# ExternalRAM.net
KiCad netlist of a schematic drawn in Altium Designer
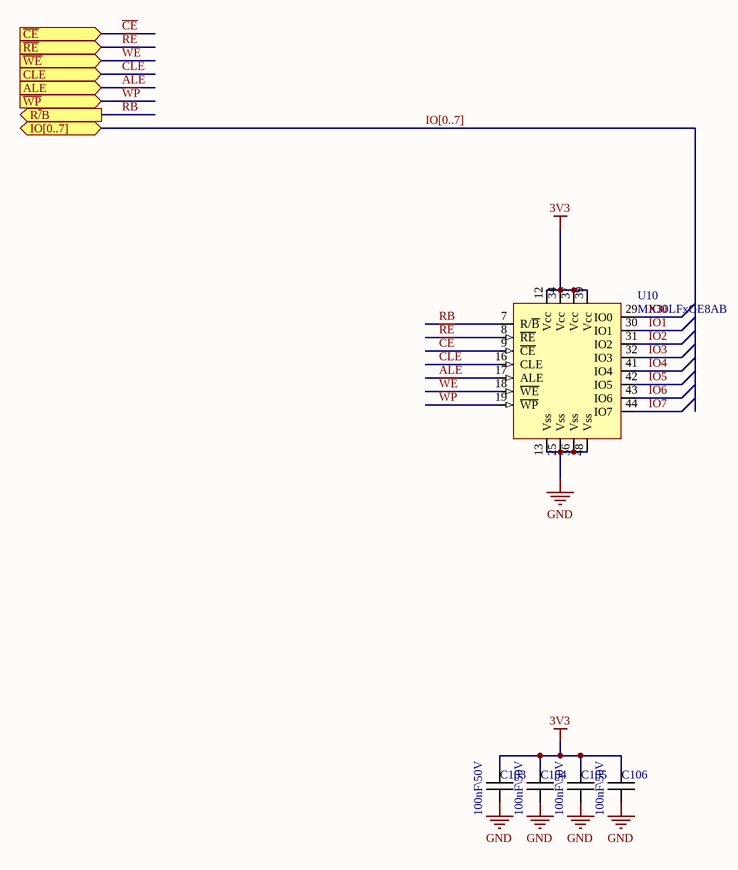
[diagram p0: ExternalRAM.SchDoc]

(export (version "E")
  (design (tool "Eeschema 10.0.6"))
  (components
    (comp (ref "C103")
      (value "100n~{F}50V")
      (footprint "SMD 0603")
      (description "CC0603KRX7R9BB104")
      (libsource (lib "Maks_lib") (part "Capasitor"))
    )
    (comp (ref "C104")
      (value "100n~{F}50V")
      (footprint "SMD 0603")
      (description "CC0603KRX7R9BB104")
      (libsource (lib "Maks_lib") (part "Capasitor"))
    )
    (comp (ref "C105")
      (value "100n~{F}50V")
      (footprint "SMD 0603")
      (description "CC0603KRX7R9BB104")
      (libsource (lib "Maks_lib") (part "Capasitor"))
    )
    (comp (ref "C106")
      (value "100n~{F}50V")
      (footprint "SMD 0603")
      (description "CC0603KRX7R9BB104")
      (libsource (lib "Maks_lib") (part "Capasitor"))
    )
    (comp (ref "U10")
      (value "MX30LFxGE8AB")
      (footprint "TSSOP50P2000X120-48N")
      (description "1G/2G/4G-bit NAND Flash Memory  (ECC-Free)")
      (libsource (lib "Maks_lib") (part "MX30LFxGE8AB"))
    )
  )
  (nets
    (net (code "1") (name "/ALE") (class "Default")
      (node (ref "U10") (pin "17") (pinfunction "ALE_17") (pintype "input"))
    )
    (net (code "2") (name "/CE") (class "Default")
      (node (ref "U10") (pin "9") (pinfunction "CE_9") (pintype "input"))
    )
    (net (code "3") (name "/CLE") (class "Default")
      (node (ref "U10") (pin "16") (pinfunction "CLE_16") (pintype "input"))
    )
    (net (code "4") (name "/IO0") (class "Default")
      (node (ref "U10") (pin "29") (pinfunction "IO0_29") (pintype "bidirectional"))
    )
    (net (code "5") (name "/IO1") (class "Default")
      (node (ref "U10") (pin "30") (pinfunction "IO1_30") (pintype "bidirectional"))
    )
    (net (code "6") (name "/IO2") (class "Default")
      (node (ref "U10") (pin "31") (pinfunction "IO2_31") (pintype "bidirectional"))
    )
    (net (code "7") (name "/IO3") (class "Default")
      (node (ref "U10") (pin "32") (pinfunction "IO3_32") (pintype "bidirectional"))
    )
    (net (code "8") (name "/IO4") (class "Default")
      (node (ref "U10") (pin "41") (pinfunction "IO4_41") (pintype "bidirectional"))
    )
    (net (code "9") (name "/IO5") (class "Default")
      (node (ref "U10") (pin "42") (pinfunction "IO5_42") (pintype "bidirectional"))
    )
    (net (code "10") (name "/IO6") (class "Default")
      (node (ref "U10") (pin "43") (pinfunction "IO6_43") (pintype "bidirectional"))
    )
    (net (code "11") (name "/IO7") (class "Default")
      (node (ref "U10") (pin "44") (pinfunction "IO7_44") (pintype "bidirectional"))
    )
    (net (code "13") (name "/RB") (class "Default")
      (node (ref "U10") (pin "7") (pinfunction "R/~{B}_7") (pintype "open_collector"))
    )
    (net (code "14") (name "/RE") (class "Default")
      (node (ref "U10") (pin "8") (pinfunction "RE_8") (pintype "input"))
    )
    (net (code "15") (name "/WE") (class "Default")
      (node (ref "U10") (pin "18") (pinfunction "WE_18") (pintype "input"))
    )
    (net (code "16") (name "/WP") (class "Default")
      (node (ref "U10") (pin "19") (pinfunction "WP_19") (pintype "input"))
    )
    (net (code "17") (name "3V3") (class "Default")
      (node (ref "C103") (pin "2") (pinfunction "2_2") (pintype "passive"))
      (node (ref "C104") (pin "2") (pinfunction "2_2") (pintype "passive"))
      (node (ref "C105") (pin "2") (pinfunction "2_2") (pintype "passive"))
      (node (ref "C106") (pin "2") (pinfunction "2_2") (pintype "passive"))
      (node (ref "U10") (pin "12") (pinfunction "Vcc_12") (pintype "passive"))
      (node (ref "U10") (pin "34") (pinfunction "Vcc_34") (pintype "passive"))
      (node (ref "U10") (pin "37") (pinfunction "Vcc_37") (pintype "passive"))
      (node (ref "U10") (pin "39") (pinfunction "Vcc_39") (pintype "passive"))
    )
    (net (code "18") (name "GND") (class "Default")
      (node (ref "C103") (pin "1") (pinfunction "1_1") (pintype "passive"))
      (node (ref "C104") (pin "1") (pinfunction "1_1") (pintype "passive"))
      (node (ref "C105") (pin "1") (pinfunction "1_1") (pintype "passive"))
      (node (ref "C106") (pin "1") (pinfunction "1_1") (pintype "passive"))
      (node (ref "U10") (pin "13") (pinfunction "Vss_13") (pintype "passive"))
      (node (ref "U10") (pin "25") (pinfunction "Vss_25") (pintype "passive"))
      (node (ref "U10") (pin "36") (pinfunction "Vss_36") (pintype "passive"))
      (node (ref "U10") (pin "48") (pinfunction "Vss_48") (pintype "passive"))
    )
  )
)
